# Damian_Edition.net
KiCad netlist of a schematic drawn in EAGLE
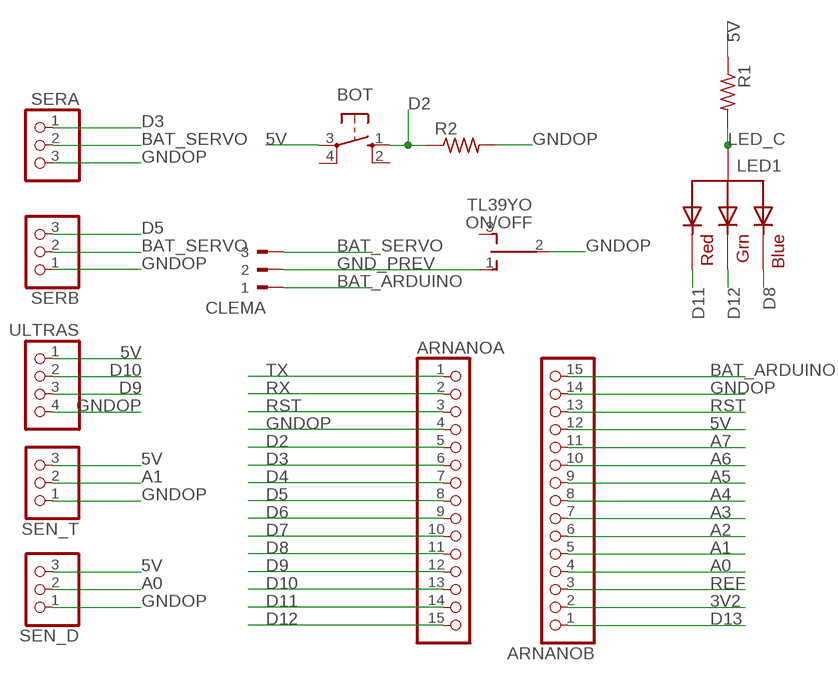
[diagram p0: schematic, sheet 1]

(export (version "E")
  (design (tool "Eeschema 10.0.6"))
  (components
    (comp (ref "ARNANOA")
      (value "PINHD-1X15")
      (footprint "eagle-import:1X15")
      (libsource (lib "eagle-import") (part "PINHD-1X15"))
    )
    (comp (ref "ARNANOB")
      (value "PINHD-1X15")
      (footprint "eagle-import:1X15")
      (libsource (lib "eagle-import") (part "PINHD-1X15"))
    )
    (comp (ref "BOT")
      (value "10-XX")
      (footprint "eagle-import:B3F-10XX")
      (fields (field (name "MPN") "B3F-1000"))
      (libsource (lib "eagle-import") (part "10-XX"))
    )
    (comp (ref "CLEMA")
      (value "90-3")
      (footprint "eagle-import:90-3")
      (libsource (lib "eagle-import") (part "90-3"))
    )
    (comp (ref "LED1")
      (value "RGBLED_CA-5MM")
      (footprint "eagle-import:LED5MMRGB")
      (libsource (lib "eagle-import") (part "RGBLED_CA-5MM"))
    )
    (comp (ref "ON/OFF")
      (value "TL39YO")
      (footprint "eagle-import:TL3XYO")
      (libsource (lib "eagle-import") (part "TL39YO"))
    )
    (comp (ref "R1")
      (value "R-US_0207/2V")
      (footprint "eagle-import:0207_2V")
      (libsource (lib "eagle-import") (part "R-US_0207/2V"))
    )
    (comp (ref "R2")
      (value "R-US_0207/2V")
      (footprint "eagle-import:0207_2V")
      (libsource (lib "eagle-import") (part "R-US_0207/2V"))
    )
    (comp (ref "SEN_D")
      (value "PINHD-1X3")
      (footprint "eagle-import:1X03")
      (libsource (lib "eagle-import") (part "PINHD-1X3"))
    )
    (comp (ref "SEN_T")
      (value "PINHD-1X3")
      (footprint "eagle-import:1X03")
      (libsource (lib "eagle-import") (part "PINHD-1X3"))
    )
    (comp (ref "SERA")
      (value "PINHD-1X3")
      (footprint "eagle-import:1X03")
      (libsource (lib "eagle-import") (part "PINHD-1X3"))
    )
    (comp (ref "SERB")
      (value "PINHD-1X3")
      (footprint "eagle-import:1X03")
      (libsource (lib "eagle-import") (part "PINHD-1X3"))
    )
    (comp (ref "ULTRAS")
      (value "PINHD-1X4")
      (footprint "eagle-import:1X04")
      (libsource (lib "eagle-import") (part "PINHD-1X4"))
    )
  )
  (nets
    (net (code "1") (name "/3V2") (class "Default")
      (node (ref "ARNANOB") (pin "2") (pinfunction "2_2") (pintype "passive"))
    )
    (net (code "2") (name "/5V") (class "Default")
      (node (ref "ARNANOB") (pin "12") (pinfunction "12_12") (pintype "passive"))
      (node (ref "BOT") (pin "3") (pinfunction "P_3") (pintype "passive"))
      (node (ref "R1") (pin "1") (pinfunction "1_1") (pintype "passive"))
      (node (ref "SEN_D") (pin "3") (pinfunction "3_3") (pintype "passive"))
      (node (ref "SEN_T") (pin "3") (pinfunction "3_3") (pintype "passive"))
      (node (ref "ULTRAS") (pin "1") (pinfunction "1_1") (pintype "passive"))
    )
    (net (code "3") (name "/A0") (class "Default")
      (node (ref "ARNANOB") (pin "4") (pinfunction "4_4") (pintype "passive"))
      (node (ref "SEN_D") (pin "2") (pinfunction "2_2") (pintype "passive"))
    )
    (net (code "4") (name "/A1") (class "Default")
      (node (ref "ARNANOB") (pin "5") (pinfunction "5_5") (pintype "passive"))
      (node (ref "SEN_T") (pin "2") (pinfunction "2_2") (pintype "passive"))
    )
    (net (code "5") (name "/A2") (class "Default")
      (node (ref "ARNANOB") (pin "6") (pinfunction "6_6") (pintype "passive"))
    )
    (net (code "6") (name "/A3") (class "Default")
      (node (ref "ARNANOB") (pin "7") (pinfunction "7_7") (pintype "passive"))
    )
    (net (code "7") (name "/A4") (class "Default")
      (node (ref "ARNANOB") (pin "8") (pinfunction "8_8") (pintype "passive"))
    )
    (net (code "8") (name "/A5") (class "Default")
      (node (ref "ARNANOB") (pin "9") (pinfunction "9_9") (pintype "passive"))
    )
    (net (code "9") (name "/A6") (class "Default")
      (node (ref "ARNANOB") (pin "10") (pinfunction "10_10") (pintype "passive"))
    )
    (net (code "10") (name "/A7") (class "Default")
      (node (ref "ARNANOB") (pin "11") (pinfunction "11_11") (pintype "passive"))
    )
    (net (code "11") (name "/BAT_ARDUINO") (class "Default")
      (node (ref "ARNANOB") (pin "15") (pinfunction "15_15") (pintype "passive"))
      (node (ref "CLEMA") (pin "1") (pinfunction "1_1") (pintype "passive"))
    )
    (net (code "12") (name "/BAT_SERVO") (class "Default")
      (node (ref "CLEMA") (pin "3") (pinfunction "3_3") (pintype "passive"))
      (node (ref "SERA") (pin "2") (pinfunction "2_2") (pintype "passive"))
      (node (ref "SERB") (pin "2") (pinfunction "2_2") (pintype "passive"))
    )
    (net (code "13") (name "/D2") (class "Default")
      (node (ref "ARNANOA") (pin "5") (pinfunction "5_5") (pintype "passive"))
      (node (ref "BOT") (pin "1") (pinfunction "S_1") (pintype "passive"))
      (node (ref "R2") (pin "1") (pinfunction "1_1") (pintype "passive"))
    )
    (net (code "14") (name "/D3") (class "Default")
      (node (ref "ARNANOA") (pin "6") (pinfunction "6_6") (pintype "passive"))
      (node (ref "SERA") (pin "1") (pinfunction "1_1") (pintype "passive"))
    )
    (net (code "15") (name "/D4") (class "Default")
      (node (ref "ARNANOA") (pin "7") (pinfunction "7_7") (pintype "passive"))
    )
    (net (code "16") (name "/D5") (class "Default")
      (node (ref "ARNANOA") (pin "8") (pinfunction "8_8") (pintype "passive"))
      (node (ref "SERB") (pin "3") (pinfunction "3_3") (pintype "passive"))
    )
    (net (code "17") (name "/D6") (class "Default")
      (node (ref "ARNANOA") (pin "9") (pinfunction "9_9") (pintype "passive"))
    )
    (net (code "18") (name "/D7") (class "Default")
      (node (ref "ARNANOA") (pin "10") (pinfunction "10_10") (pintype "passive"))
    )
    (net (code "19") (name "/D8") (class "Default")
      (node (ref "ARNANOA") (pin "11") (pinfunction "11_11") (pintype "passive"))
      (node (ref "LED1") (pin "4") (pinfunction "BLUE_4") (pintype "bidirectional"))
    )
    (net (code "20") (name "/D9") (class "Default")
      (node (ref "ARNANOA") (pin "12") (pinfunction "12_12") (pintype "passive"))
      (node (ref "ULTRAS") (pin "3") (pinfunction "3_3") (pintype "passive"))
    )
    (net (code "21") (name "/D10") (class "Default")
      (node (ref "ARNANOA") (pin "13") (pinfunction "13_13") (pintype "passive"))
      (node (ref "ULTRAS") (pin "2") (pinfunction "2_2") (pintype "passive"))
    )
    (net (code "22") (name "/D11") (class "Default")
      (node (ref "ARNANOA") (pin "14") (pinfunction "14_14") (pintype "passive"))
      (node (ref "LED1") (pin "1") (pinfunction "RED_1") (pintype "bidirectional"))
    )
    (net (code "23") (name "/D12") (class "Default")
      (node (ref "ARNANOA") (pin "15") (pinfunction "15_15") (pintype "passive"))
      (node (ref "LED1") (pin "3") (pinfunction "GREEN_3") (pintype "bidirectional"))
    )
    (net (code "24") (name "/D13") (class "Default")
      (node (ref "ARNANOB") (pin "1") (pinfunction "1_1") (pintype "passive"))
    )
    (net (code "25") (name "/GNDOP") (class "Default")
      (node (ref "ARNANOA") (pin "4") (pinfunction "4_4") (pintype "passive"))
      (node (ref "ARNANOB") (pin "14") (pinfunction "14_14") (pintype "passive"))
      (node (ref "ON/OFF") (pin "2") (pinfunction "P_2") (pintype "passive"))
      (node (ref "R2") (pin "2") (pinfunction "2_2") (pintype "passive"))
      (node (ref "SEN_D") (pin "1") (pinfunction "1_1") (pintype "passive"))
      (node (ref "SEN_T") (pin "1") (pinfunction "1_1") (pintype "passive"))
      (node (ref "SERA") (pin "3") (pinfunction "3_3") (pintype "passive"))
      (node (ref "SERB") (pin "1") (pinfunction "1_1") (pintype "passive"))
      (node (ref "ULTRAS") (pin "4") (pinfunction "4_4") (pintype "passive"))
    )
    (net (code "26") (name "/GND_PREV") (class "Default")
      (node (ref "CLEMA") (pin "2") (pinfunction "2_2") (pintype "passive"))
      (node (ref "ON/OFF") (pin "1") (pinfunction "O_1") (pintype "passive"))
    )
    (net (code "27") (name "/LED_C") (class "Default")
      (node (ref "LED1") (pin "2") (pinfunction "VCC_2") (pintype "bidirectional"))
      (node (ref "R1") (pin "2") (pinfunction "2_2") (pintype "passive"))
    )
    (net (code "28") (name "/REF") (class "Default")
      (node (ref "ARNANOB") (pin "3") (pinfunction "3_3") (pintype "passive"))
    )
    (net (code "29") (name "/RST") (class "Default")
      (node (ref "ARNANOA") (pin "3") (pinfunction "3_3") (pintype "passive"))
      (node (ref "ARNANOB") (pin "13") (pinfunction "13_13") (pintype "passive"))
    )
    (net (code "30") (name "/RX") (class "Default")
      (node (ref "ARNANOA") (pin "2") (pinfunction "2_2") (pintype "passive"))
    )
    (net (code "31") (name "/TX") (class "Default")
      (node (ref "ARNANOA") (pin "1") (pinfunction "1_1") (pintype "passive"))
    )
    (net (code "32") (name "unconnected-(BOT-P1-Pad4)") (class "Default")
      (node (ref "BOT") (pin "4") (pinfunction "P1_4") (pintype "passive"))
    )
    (net (code "33") (name "unconnected-(BOT-S1-Pad2)") (class "Default")
      (node (ref "BOT") (pin "2") (pinfunction "S1_2") (pintype "passive"))
    )
    (net (code "34") (name "unconnected-(ON/OFF-S-Pad3)") (class "Default")
      (node (ref "ON/OFF") (pin "3") (pinfunction "S_3") (pintype "passive"))
    )
  )
)
